# WifiAntenna.net
KiCad netlist of a schematic drawn in Altium Designer
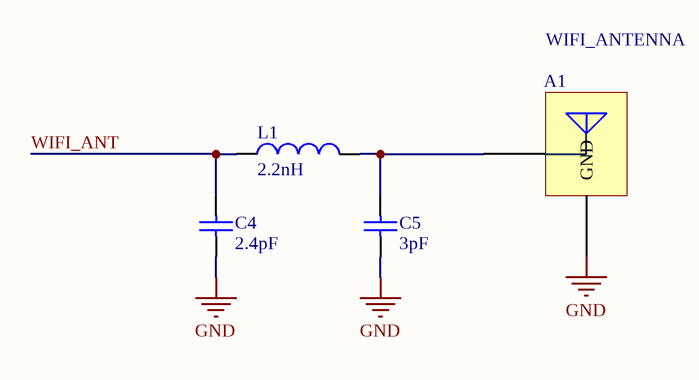
[diagram p0: WifiAntenna.SchDoc]

(export (version "E")
  (design (tool "Eeschema 10.0.6"))
  (components
    (comp (ref "A1")
      (value "WIFI_ANTENNA")
      (footprint "PCB-wx81mnio3p969u8b8u4u-1")
      (description "Meandered Inverted-F Antenna")
      (libsource (lib "CommunityVault") (part "CMP-nvfputv9e4hvqhxbgt68-5"))
    )
    (comp (ref "C4")
      (value "2.4pF")
      (footprint "CAPC1005X55X25ML05T10")
      (description "CAP CER 2.4PF 50V NP0 0402")
      (fields (field (name "MANUFACTURER PART NUMBER") "GJM1555C1H2R4CB01D"))
      (libsource (lib "CommunityVault") (part "CAP-2"))
    )
    (comp (ref "C5")
      (value "3pF")
      (footprint "CAPC1005X55X25ML05T10")
      (description "Multilayer Ceramic Capacitors MLCC - SMD/SMT 0402 3.0pF 50volts C0G +/-0.25pF")
      (fields (field (name "MANUFACTURER PART NUMBER") "GRM1555C1H3R0CA01D"))
      (libsource (lib "CommunityVault") (part "CAP-2"))
    )
    (comp (ref "L1")
      (value "2.2nH")
      (footprint "PCB-vg5vda2wcniu3fh2gltx-1")
      (description "Inductor RF Chip Thin Film 2.2nH 0.1nH 500MHz 14Q-Factor 600mA 150mOhm DCR 0201 Paper T/R")
      (fields (field (name "MANUFACTURER PART NUMBER") "LQP03TN2N2B02D"))
      (libsource (lib "CommunityVault") (part "SYM-80494860bc425f8e-1"))
    )
  )
  (nets
    (net (code "1") (name "/WIFI_ANT") (class "Default")
      (node (ref "C4") (pin "2") (pinfunction "2_2") (pintype "passive"))
      (node (ref "L1") (pin "1") (pinfunction "1_1") (pintype "passive"))
    )
    (net (code "2") (name "GND") (class "Default")
      (node (ref "A1") (pin "2") (pinfunction "GND_2") (pintype "passive"))
      (node (ref "C4") (pin "1") (pinfunction "1_1") (pintype "passive"))
      (node (ref "C5") (pin "1") (pinfunction "1_1") (pintype "passive"))
    )
    (net (code "3") (name "Net-(A1-A)") (class "Default")
      (node (ref "A1") (pin "1") (pinfunction "A_1") (pintype "passive"))
      (node (ref "C5") (pin "2") (pinfunction "2_2") (pintype "passive"))
      (node (ref "L1") (pin "2") (pinfunction "2_2") (pintype "passive"))
    )
  )
)
